# switch.net
KiCad netlist of a schematic drawn in Altium Designer
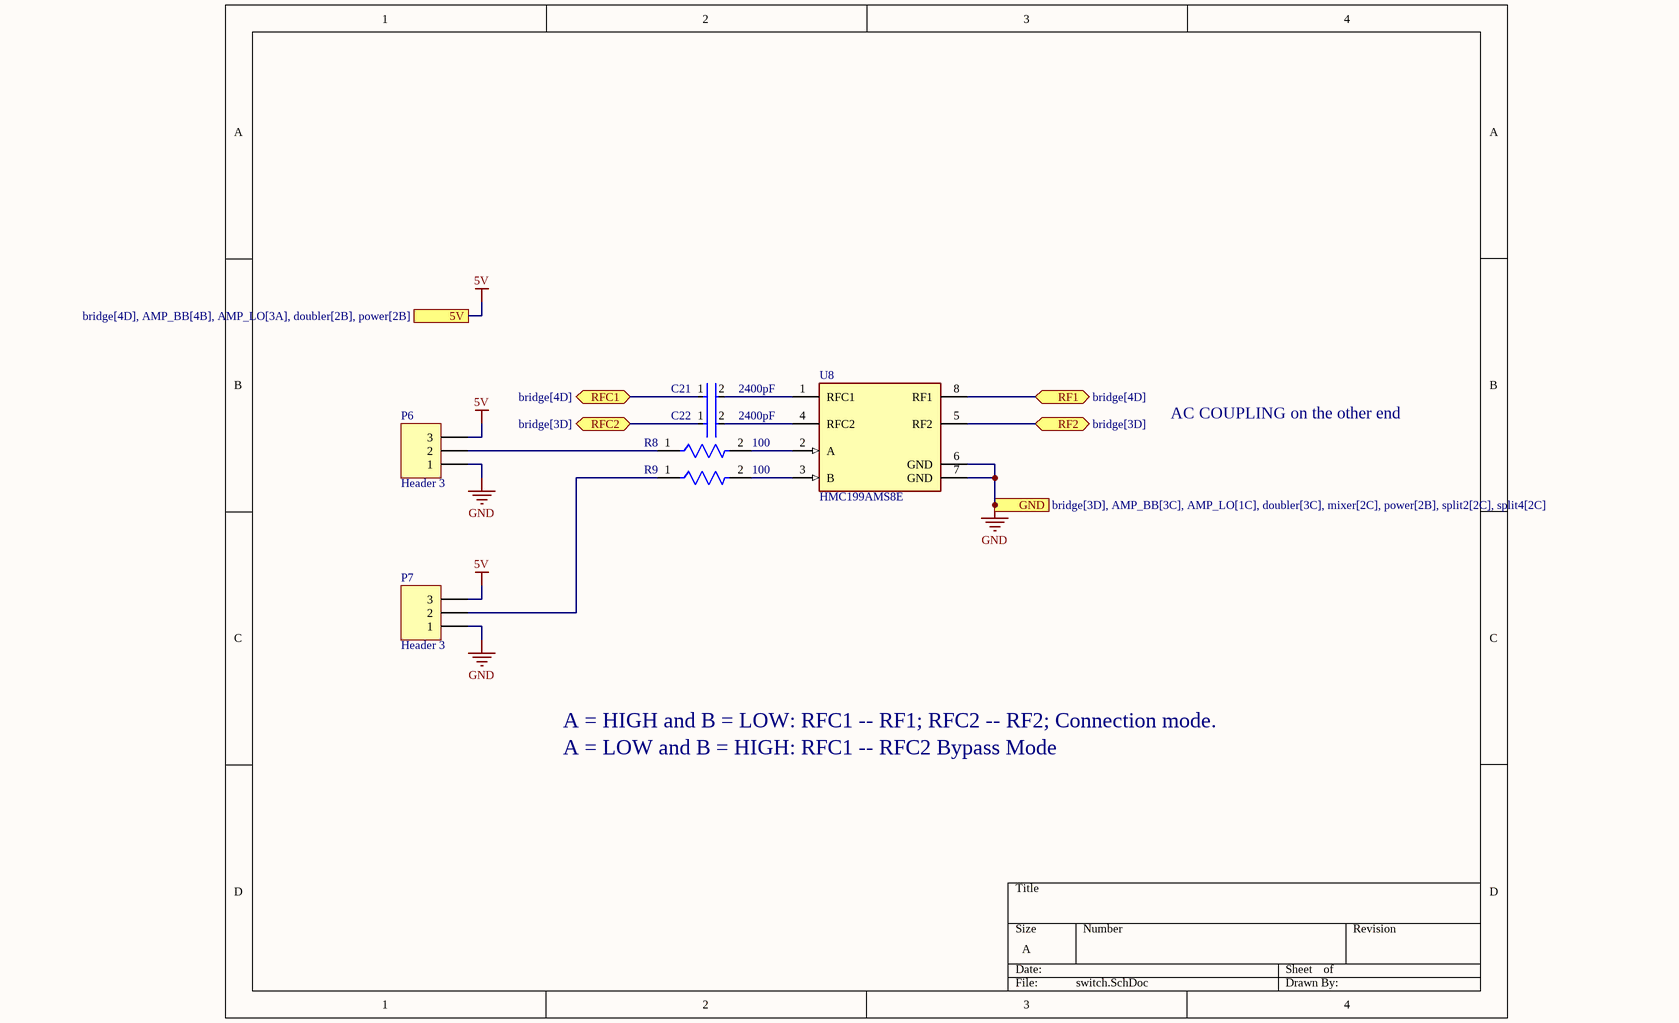
[diagram p0: switch.SchDoc]

(export (version "E")
  (design (tool "Eeschema 10.0.6"))
  (components
    (comp (ref "C21")
      (value "2400pF")
      (footprint "FP-GRM188-0_1-e0_2_0_5-MFG")
      (fields (field (name "TOLERANCE") "5%") (field (name "VOLTAGE") "50V"))
      (libsource (lib "Altium Content Vault") (part "11868f565c42a9108669ba33697ecf6"))
    )
    (comp (ref "C22")
      (value "2400pF")
      (footprint "FP-GRM188-0_1-e0_2_0_5-MFG")
      (fields (field (name "TOLERANCE") "5%") (field (name "VOLTAGE") "50V"))
      (libsource (lib "Altium Content Vault") (part "11868f565c42a9108669ba33697ecf6"))
    )
    (comp (ref "P6")
      (value "Header 3")
      (footprint "HDR1X3")
      (description "Header, 3-Pin")
      (fields (field (name "PUBLISHER") "Altium Limited"))
      (libsource (lib "University of California, San Diego") (part "Header 3H"))
    )
    (comp (ref "P7")
      (value "Header 3")
      (footprint "HDR1X3")
      (description "Header, 3-Pin")
      (fields (field (name "PUBLISHER") "Altium Limited"))
      (libsource (lib "University of California, San Diego") (part "Header 3H"))
    )
    (comp (ref "R8")
      (value "100")
      (footprint "FP-RC0603-0_55-MFG")
      (description "RES SMD 100 OHM 5% 1/10W 0603")
      (fields (field (name "TOLERANCE") "5%"))
      (libsource (lib "Altium Content Vault") (part "1029c3af85768c4190bb7ad29bc67b5"))
    )
    (comp (ref "R9")
      (value "100")
      (footprint "FP-RC0603-0_55-MFG")
      (description "RES SMD 100 OHM 5% 1/10W 0603")
      (fields (field (name "TOLERANCE") "5%"))
      (libsource (lib "Altium Content Vault") (part "1029c3af85768c4190bb7ad29bc67b5"))
    )
    (comp (ref "U8")
      (value "HMC199AMS8E")
      (footprint "FP-RM-8-IPC_A")
      (description "IC RF SWITCH SPDT 2.5GHZ 8MSOP")
      (libsource (lib "Altium Content Vault") (part "6843bc3350703c057c5d36bf5f7cd74"))
    )
  )
  (nets
    (net (code "1") (name "/RF1") (class "Default")
      (node (ref "U8") (pin "8") (pinfunction "RF1_8") (pintype "passive"))
    )
    (net (code "2") (name "/RF2") (class "Default")
      (node (ref "U8") (pin "5") (pinfunction "RF2_5") (pintype "passive"))
    )
    (net (code "3") (name "/RFC1") (class "Default")
      (node (ref "C21") (pin "1") (pinfunction "1_1") (pintype "passive"))
    )
    (net (code "4") (name "/RFC2") (class "Default")
      (node (ref "C22") (pin "1") (pinfunction "1_1") (pintype "passive"))
    )
    (net (code "5") (name "5V") (class "Default")
      (node (ref "P6") (pin "3") (pinfunction "3_3") (pintype "passive"))
      (node (ref "P7") (pin "3") (pinfunction "3_3") (pintype "passive"))
    )
    (net (code "6") (name "GND") (class "Default")
      (node (ref "P6") (pin "1") (pinfunction "1_1") (pintype "passive"))
      (node (ref "P7") (pin "1") (pinfunction "1_1") (pintype "passive"))
      (node (ref "U8") (pin "6") (pinfunction "GND_6") (pintype "power_in"))
      (node (ref "U8") (pin "7") (pinfunction "GND_7") (pintype "power_in"))
    )
    (net (code "7") (name "Net-(P6-Pad2)") (class "Default")
      (node (ref "P6") (pin "2") (pinfunction "2_2") (pintype "passive"))
      (node (ref "R8") (pin "1") (pinfunction "1_1") (pintype "passive"))
    )
    (net (code "8") (name "Net-(P7-Pad2)") (class "Default")
      (node (ref "P7") (pin "2") (pinfunction "2_2") (pintype "passive"))
      (node (ref "R9") (pin "1") (pinfunction "1_1") (pintype "passive"))
    )
    (net (code "9") (name "Net-(U8-A)") (class "Default")
      (node (ref "R8") (pin "2") (pinfunction "2_2") (pintype "passive"))
      (node (ref "U8") (pin "2") (pinfunction "A_2") (pintype "input"))
    )
    (net (code "10") (name "Net-(U8-B)") (class "Default")
      (node (ref "R9") (pin "2") (pinfunction "2_2") (pintype "passive"))
      (node (ref "U8") (pin "3") (pinfunction "B_3") (pintype "input"))
    )
    (net (code "11") (name "Net-(U8-RFC1)") (class "Default")
      (node (ref "C21") (pin "2") (pinfunction "2_2") (pintype "passive"))
      (node (ref "U8") (pin "1") (pinfunction "RFC1_1") (pintype "passive"))
    )
    (net (code "12") (name "Net-(U8-RFC2)") (class "Default")
      (node (ref "C22") (pin "2") (pinfunction "2_2") (pintype "passive"))
      (node (ref "U8") (pin "4") (pinfunction "RFC2_4") (pintype "passive"))
    )
  )
)
